# MCU_IO.net
KiCad netlist of a schematic drawn in Altium Designer
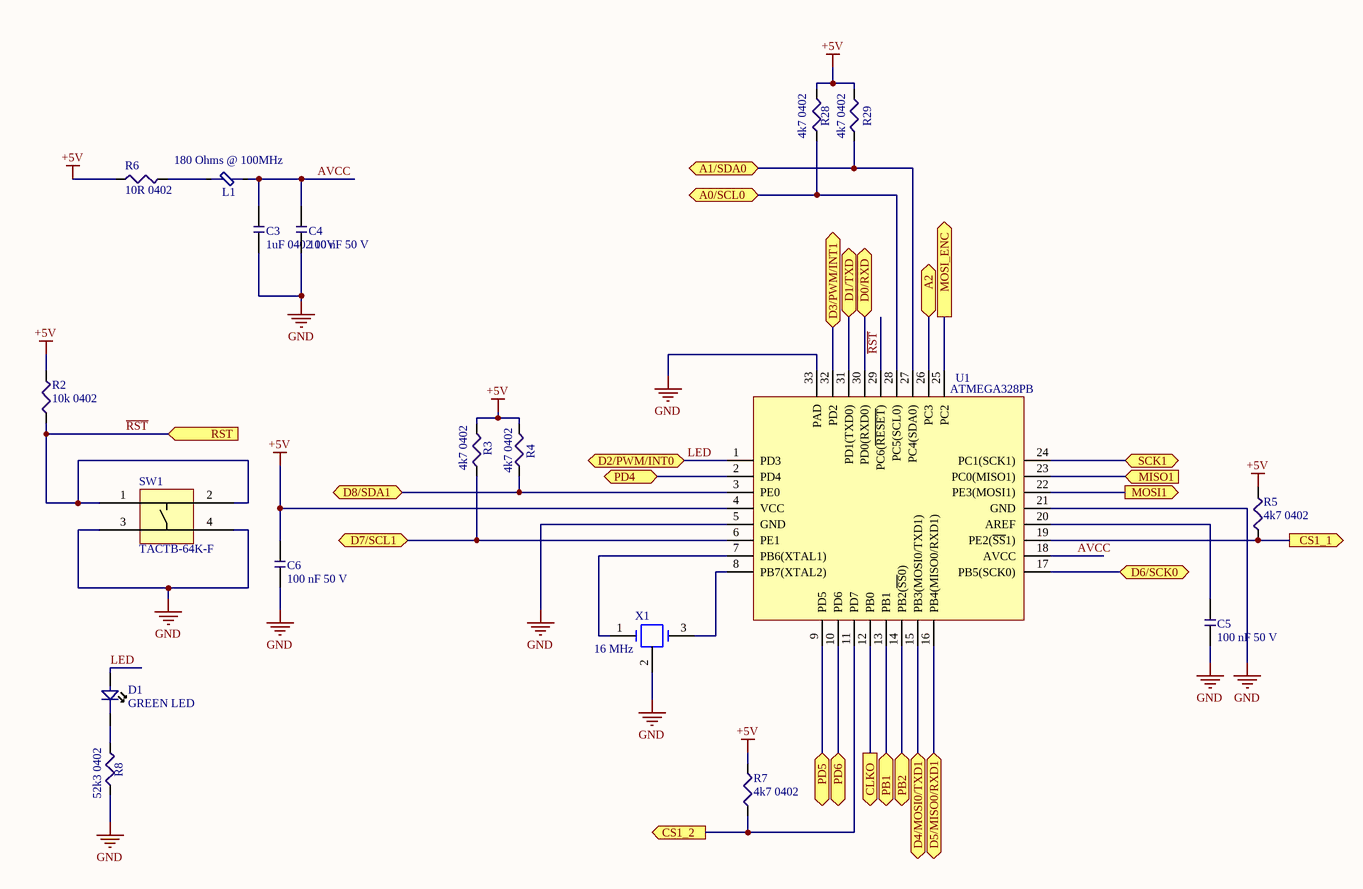
[diagram p0: MCU+IO.SchDoc]

(export (version "E")
  (design (tool "Eeschema 10.0.6"))
  (components
    (comp (ref "C3")
      (value "1uF 0402 10V")
      (footprint "CAP_0402")
      (description "1uF 0402 10V 10% X5R")
      (fields (field (name "TOLERANCE") "10%") (field (name "VOLTAGE") "10 V"))
      (libsource (lib "ON Development Vault") (part "Capacitor"))
    )
    (comp (ref "C4")
      (value "100 nF 50 V")
      (footprint "CAP_0402")
      (description "Multilayer Ceramic Capacitors MLCC - SMD/SMT .1uF 50Volts X7R +/-10% 0402 STD")
      (fields (field (name "TOLERANCE") "10%") (field (name "VOLTAGE") "50 V"))
      (libsource (lib "ON Development Vault") (part "Capacitor"))
    )
    (comp (ref "C5")
      (value "100 nF 50 V")
      (footprint "CAP_0402")
      (description "Multilayer Ceramic Capacitors MLCC - SMD/SMT .1uF 50Volts X7R +/-10% 0402 STD")
      (fields (field (name "TOLERANCE") "10%") (field (name "VOLTAGE") "50 V"))
      (libsource (lib "ON Development Vault") (part "Capacitor"))
    )
    (comp (ref "C6")
      (value "100 nF 50 V")
      (footprint "CAP_0402")
      (description "Multilayer Ceramic Capacitors MLCC - SMD/SMT .1uF 50Volts X7R +/-10% 0402 STD")
      (fields (field (name "TOLERANCE") "10%") (field (name "VOLTAGE") "50 V"))
      (libsource (lib "ON Development Vault") (part "Capacitor"))
    )
    (comp (ref "D1")
      (value "GREEN LED")
      (footprint "0402 LED")
      (description "0402 SMD LED")
      (fields (field (name "MFG. PART NUMBER") "LTST-C281KGKT"))
      (libsource (lib "ON Development Vault") (part "LED"))
    )
    (comp (ref "L1")
      (value "180 Ohms @ 100MHz")
      (footprint "IND_0603")
      (description "FERRITE BEAD 180 OHM 0603 1LN")
      (fields (field (name "MFG. PART NUMBER") "BLM18PG181SN1D"))
      (libsource (lib "ON Development Vault") (part "Ferrite"))
    )
    (comp (ref "R2")
      (value "10k 0402")
      (footprint "RES_0402")
      (description "RES SMD 10K OHM 1% 1/16W 0402")
      (fields (field (name "POWER") "1/16 W") (field (name "TOLERANCE") "1 %"))
      (libsource (lib "ON Development Vault") (part "Resistor"))
    )
    (comp (ref "R3")
      (value "4k7 0402")
      (footprint "RES_0402")
      (description "RES SMD 4.7K OHM 1% 1/16W 0402")
      (fields (field (name "POWER") "1/16W") (field (name "TOLERANCE") "1"))
      (libsource (lib "ON Development Vault") (part "Resistor"))
    )
    (comp (ref "R4")
      (value "4k7 0402")
      (footprint "RES_0402")
      (description "RES SMD 4.7K OHM 1% 1/16W 0402")
      (fields (field (name "POWER") "1/16W") (field (name "TOLERANCE") "1"))
      (libsource (lib "ON Development Vault") (part "Resistor"))
    )
    (comp (ref "R5")
      (value "4k7 0402")
      (footprint "RES_0402")
      (description "RES SMD 4.7K OHM 1% 1/16W 0402")
      (fields (field (name "POWER") "1/16W") (field (name "TOLERANCE") "1"))
      (libsource (lib "ON Development Vault") (part "Resistor"))
    )
    (comp (ref "R6")
      (value "10R 0402")
      (footprint "RES_0402")
      (description "RES SMD 10 OHM 1% 1/16W 0402")
      (fields (field (name "POWER") "63mW") (field (name "TOLERANCE") "1%"))
      (libsource (lib "ON Development Vault") (part "Resistor"))
    )
    (comp (ref "R7")
      (value "4k7 0402")
      (footprint "RES_0402")
      (description "RES SMD 4.7K OHM 1% 1/16W 0402")
      (fields (field (name "POWER") "1/16W") (field (name "TOLERANCE") "1"))
      (libsource (lib "ON Development Vault") (part "Resistor"))
    )
    (comp (ref "R8")
      (value "52k3 0402")
      (footprint "RES_0402")
      (description "RES SMD 52.3K OHM 1% 1/16W 0402")
      (fields (field (name "POWER") "1/16 W") (field (name "TOLERANCE") "1 %"))
      (libsource (lib "ON Development Vault") (part "Resistor"))
    )
    (comp (ref "R28")
      (value "4k7 0402")
      (footprint "RES_0402")
      (description "RES SMD 4.7K OHM 1% 1/16W 0402")
      (fields (field (name "POWER") "1/16W") (field (name "TOLERANCE") "1"))
      (libsource (lib "ON Development Vault") (part "Resistor"))
    )
    (comp (ref "R29")
      (value "4k7 0402")
      (footprint "RES_0402")
      (description "RES SMD 4.7K OHM 1% 1/16W 0402")
      (fields (field (name "POWER") "1/16W") (field (name "TOLERANCE") "1"))
      (libsource (lib "ON Development Vault") (part "Resistor"))
    )
    (comp (ref "SW1")
      (value "TACTB-64K-F")
      (footprint "TACTB-64K-F")
      (description "Microswitch TACT; SPST-NO; Positions:2; 0.05A/12VDC;")
      (libsource (lib "ON Development Vault") (part "CMP-013-0002-1"))
    )
    (comp (ref "U1")
      (value "ATMEGA328PB")
      (footprint "QFN50P500X500X90_HS-33N")
      (description "IC MCU 8BIT 32KB FLASH 32TQFP")
      (libsource (lib "ON Development Vault") (part "ATmega328PB"))
    )
    (comp (ref "X1")
      (value "16 MHz")
      (footprint "CSTCE16XTAL")
      (description "CER RES 16.0000MHZ 15PF SMD")
      (fields (field (name "MFG. PART NUMBER") "CSTCE16M0V53-R0"))
      (libsource (lib "ON Development Vault") (part "Xtal 3-pin"))
    )
  )
  (nets
    (net (code "1") (name "+5V") (class "Default")
      (node (ref "C6") (pin "1") (pinfunction "1_1") (pintype "passive"))
      (node (ref "R2") (pin "2") (pinfunction "2_2") (pintype "passive"))
      (node (ref "R28") (pin "2") (pinfunction "2_2") (pintype "passive"))
      (node (ref "R29") (pin "2") (pinfunction "2_2") (pintype "passive"))
      (node (ref "R3") (pin "2") (pinfunction "2_2") (pintype "passive"))
      (node (ref "R4") (pin "2") (pinfunction "2_2") (pintype "passive"))
      (node (ref "R5") (pin "2") (pinfunction "2_2") (pintype "passive"))
      (node (ref "R6") (pin "1") (pinfunction "1_1") (pintype "passive"))
      (node (ref "R7") (pin "2") (pinfunction "2_2") (pintype "passive"))
      (node (ref "U1") (pin "4") (pinfunction "VCC_4") (pintype "passive"))
    )
    (net (code "2") (name "/A0{slash}SCL0") (class "Default")
      (node (ref "R28") (pin "1") (pinfunction "1_1") (pintype "passive"))
      (node (ref "U1") (pin "28") (pinfunction "PC5(SCL0)_28") (pintype "passive"))
    )
    (net (code "3") (name "/A1{slash}SDA0") (class "Default")
      (node (ref "R29") (pin "1") (pinfunction "1_1") (pintype "passive"))
      (node (ref "U1") (pin "27") (pinfunction "PC4(SDA0)_27") (pintype "passive"))
    )
    (net (code "4") (name "/A2") (class "Default")
      (node (ref "U1") (pin "26") (pinfunction "PC3_26") (pintype "passive"))
    )
    (net (code "5") (name "/AVCC") (class "Default")
      (node (ref "C3") (pin "2") (pinfunction "2_2") (pintype "passive"))
      (node (ref "C4") (pin "1") (pinfunction "1_1") (pintype "passive"))
      (node (ref "L1") (pin "2") (pinfunction "2_2") (pintype "passive"))
      (node (ref "U1") (pin "18") (pinfunction "AVCC_18") (pintype "passive"))
    )
    (net (code "6") (name "/CLKO") (class "Default")
      (node (ref "U1") (pin "12") (pinfunction "PB0_12") (pintype "passive"))
    )
    (net (code "7") (name "/CS1_1") (class "Default")
      (node (ref "R5") (pin "1") (pinfunction "1_1") (pintype "passive"))
      (node (ref "U1") (pin "19") (pinfunction "PE2(~{SS}1)_19") (pintype "passive"))
    )
    (net (code "8") (name "/CS1_2") (class "Default")
      (node (ref "R7") (pin "1") (pinfunction "1_1") (pintype "passive"))
      (node (ref "U1") (pin "11") (pinfunction "PD7_11") (pintype "passive"))
    )
    (net (code "9") (name "/D0{slash}RXD") (class "Default")
      (node (ref "U1") (pin "30") (pinfunction "PD0(RXD0)_30") (pintype "passive"))
    )
    (net (code "10") (name "/D1{slash}TXD") (class "Default")
      (node (ref "U1") (pin "31") (pinfunction "PD1(TXD0)_31") (pintype "passive"))
    )
    (net (code "11") (name "/D3{slash}PWM{slash}INT1") (class "Default")
      (node (ref "U1") (pin "32") (pinfunction "PD2_32") (pintype "passive"))
    )
    (net (code "12") (name "/D4{slash}MOSI0{slash}TXD1") (class "Default")
      (node (ref "U1") (pin "15") (pinfunction "PB3(MOSI0/TXD1)_15") (pintype "passive"))
    )
    (net (code "13") (name "/D5{slash}MISO0{slash}RXD1") (class "Default")
      (node (ref "U1") (pin "16") (pinfunction "PB4(MISO0/RXD1)_16") (pintype "passive"))
    )
    (net (code "14") (name "/D6{slash}SCK0") (class "Default")
      (node (ref "U1") (pin "17") (pinfunction "PB5(SCK0)_17") (pintype "passive"))
    )
    (net (code "15") (name "/D7{slash}SCL1") (class "Default")
      (node (ref "R3") (pin "1") (pinfunction "1_1") (pintype "passive"))
      (node (ref "U1") (pin "6") (pinfunction "PE1_6") (pintype "passive"))
    )
    (net (code "16") (name "/D8{slash}SDA1") (class "Default")
      (node (ref "R4") (pin "1") (pinfunction "1_1") (pintype "passive"))
      (node (ref "U1") (pin "3") (pinfunction "PE0_3") (pintype "passive"))
    )
    (net (code "17") (name "/LED") (class "Default")
      (node (ref "D1") (pin "1") (pinfunction "1_1") (pintype "passive"))
      (node (ref "U1") (pin "1") (pinfunction "PD3_1") (pintype "passive"))
    )
    (net (code "18") (name "/MISO1") (class "Default")
      (node (ref "U1") (pin "23") (pinfunction "PC0(MISO1)_23") (pintype "passive"))
    )
    (net (code "19") (name "/MOSI1") (class "Default")
      (node (ref "U1") (pin "22") (pinfunction "PE3(MOSI1)_22") (pintype "passive"))
    )
    (net (code "20") (name "/MOSI_ENC") (class "Default")
      (node (ref "U1") (pin "25") (pinfunction "PC2_25") (pintype "passive"))
    )
    (net (code "21") (name "/PB1") (class "Default")
      (node (ref "U1") (pin "13") (pinfunction "PB1_13") (pintype "passive"))
    )
    (net (code "22") (name "/PB2") (class "Default")
      (node (ref "U1") (pin "14") (pinfunction "PB2(~{SS}0)_14") (pintype "passive"))
    )
    (net (code "23") (name "/PD4") (class "Default")
      (node (ref "U1") (pin "2") (pinfunction "PD4_2") (pintype "passive"))
    )
    (net (code "24") (name "/PD5") (class "Default")
      (node (ref "U1") (pin "9") (pinfunction "PD5_9") (pintype "passive"))
    )
    (net (code "25") (name "/PD6") (class "Default")
      (node (ref "U1") (pin "10") (pinfunction "PD6_10") (pintype "passive"))
    )
    (net (code "26") (name "/SCK1") (class "Default")
      (node (ref "U1") (pin "24") (pinfunction "PC1(SCK1)_24") (pintype "passive"))
    )
    (net (code "27") (name "/~{RST}") (class "Default")
      (node (ref "R2") (pin "1") (pinfunction "1_1") (pintype "passive"))
      (node (ref "SW1") (pin "1") (pinfunction "1_1") (pintype "passive"))
      (node (ref "SW1") (pin "2") (pinfunction "2_2") (pintype "passive"))
      (node (ref "U1") (pin "29") (pinfunction "PC6(~{RESET})_29") (pintype "passive"))
    )
    (net (code "28") (name "GND") (class "Default")
      (node (ref "C3") (pin "1") (pinfunction "1_1") (pintype "passive"))
      (node (ref "C4") (pin "2") (pinfunction "2_2") (pintype "passive"))
      (node (ref "C5") (pin "2") (pinfunction "2_2") (pintype "passive"))
      (node (ref "C6") (pin "2") (pinfunction "2_2") (pintype "passive"))
      (node (ref "R8") (pin "1") (pinfunction "1_1") (pintype "passive"))
      (node (ref "SW1") (pin "3") (pinfunction "3_3") (pintype "passive"))
      (node (ref "SW1") (pin "4") (pinfunction "4_4") (pintype "passive"))
      (node (ref "U1") (pin "21") (pinfunction "GND_21") (pintype "passive"))
      (node (ref "U1") (pin "33") (pinfunction "PAD_33") (pintype "passive"))
      (node (ref "U1") (pin "5") (pinfunction "GND_5") (pintype "passive"))
      (node (ref "X1") (pin "2") (pinfunction "GND_2") (pintype "passive"))
    )
    (net (code "29") (name "Net-(D1-Pad2)") (class "Default")
      (node (ref "D1") (pin "2") (pinfunction "2_2") (pintype "passive"))
      (node (ref "R8") (pin "2") (pinfunction "2_2") (pintype "passive"))
    )
    (net (code "30") (name "Net-(L1-Pad1)") (class "Default")
      (node (ref "L1") (pin "1") (pinfunction "1_1") (pintype "passive"))
      (node (ref "R6") (pin "2") (pinfunction "2_2") (pintype "passive"))
    )
    (net (code "31") (name "Net-(U1-AREF)") (class "Default")
      (node (ref "C5") (pin "1") (pinfunction "1_1") (pintype "passive"))
      (node (ref "U1") (pin "20") (pinfunction "AREF_20") (pintype "passive"))
    )
    (net (code "32") (name "Net-(U1-PB6(XTAL1))") (class "Default")
      (node (ref "U1") (pin "7") (pinfunction "PB6(XTAL1)_7") (pintype "passive"))
      (node (ref "X1") (pin "1") (pinfunction "OSC1_1") (pintype "passive"))
    )
    (net (code "33") (name "Net-(U1-PB7(XTAL2))") (class "Default")
      (node (ref "U1") (pin "8") (pinfunction "PB7(XTAL2)_8") (pintype "passive"))
      (node (ref "X1") (pin "3") (pinfunction "OSC2_3") (pintype "passive"))
    )
  )
)
